# piezo-buffer-and-preamp-ritter_coppercla.net
KiCad netlist of a schematic drawn in EAGLE
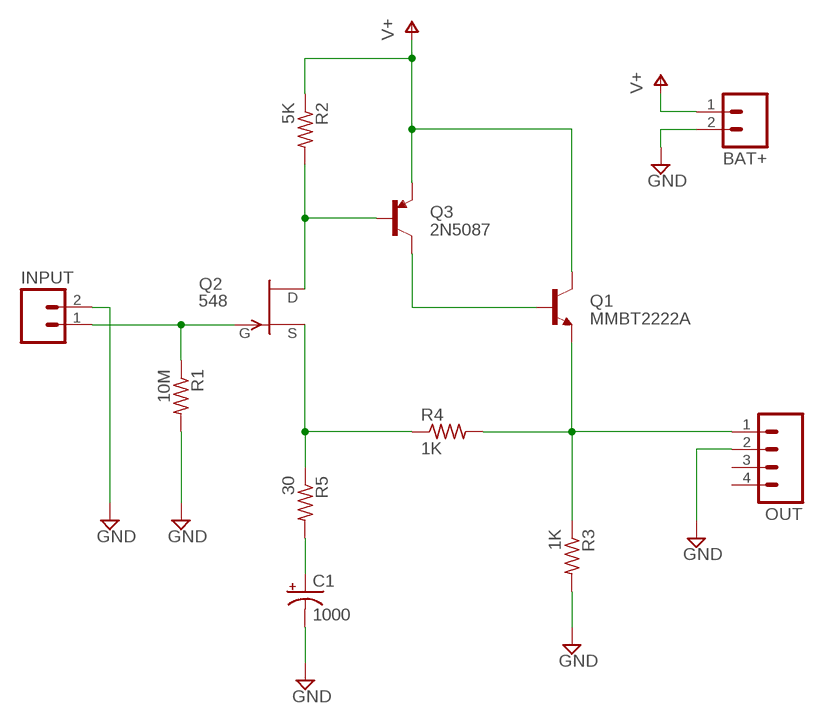
[diagram p0: schematic, sheet 1]

(export (version "E")
  (design (tool "Eeschema 10.0.6"))
  (components
    (comp (ref "BAT+")
      (value "M02LOCK")
      (footprint "eagle-import:1X02_LOCK")
      (libsource (lib "eagle-import") (part "M02LOCK"))
    )
    (comp (ref "C1")
      (value "1000")
      (footprint "eagle-import:CPOL-RADIAL-10UF-25V")
      (libsource (lib "eagle-import") (part "CAP_POLPTH2"))
    )
    (comp (ref "INPUT")
      (value "M02LOCK")
      (footprint "eagle-import:1X02_LOCK")
      (libsource (lib "eagle-import") (part "M02LOCK"))
    )
    (comp (ref "OUT")
      (value "M04PTH")
      (footprint "eagle-import:1X04")
      (libsource (lib "eagle-import") (part "M04PTH"))
    )
    (comp (ref "Q1")
      (value "MMBT2222A")
      (footprint "eagle-import:TO-92")
      (libsource (lib "eagle-import") (part "TRANSISTOR_NPNTO92"))
    )
    (comp (ref "Q2")
      (value "548")
      (footprint "eagle-import:TO-92")
      (libsource (lib "eagle-import") (part "?548"))
    )
    (comp (ref "Q3")
      (value "2N5087")
      (footprint "eagle-import:TO-92")
      (libsource (lib "eagle-import") (part "TRANSISTOR_PNPTO92"))
    )
    (comp (ref "R1")
      (value "10M")
      (footprint "eagle-import:VMTA55")
      (libsource (lib "eagle-import") (part "R-US_VMTA55"))
    )
    (comp (ref "R2")
      (value "5K")
      (footprint "eagle-import:VMTA55")
      (libsource (lib "eagle-import") (part "R-US_VMTA55"))
    )
    (comp (ref "R3")
      (value "1K")
      (footprint "eagle-import:VMTA55")
      (libsource (lib "eagle-import") (part "R-US_VMTA55"))
    )
    (comp (ref "R4")
      (value "1K")
      (footprint "eagle-import:VMTA55")
      (libsource (lib "eagle-import") (part "R-US_VMTA55"))
    )
    (comp (ref "R5")
      (value "30")
      (footprint "eagle-import:VMTA55")
      (libsource (lib "eagle-import") (part "R-US_VMTA55"))
    )
  )
  (nets
    (net (code "1") (name "GND") (class "Default")
      (node (ref "BAT+") (pin "2") (pinfunction "2_2") (pintype "passive"))
      (node (ref "C1") (pin "2") (pinfunction "-_2") (pintype "passive"))
      (node (ref "INPUT") (pin "2") (pinfunction "2_2") (pintype "passive"))
      (node (ref "OUT") (pin "2") (pinfunction "2_2") (pintype "passive"))
      (node (ref "R1") (pin "2") (pinfunction "2_2") (pintype "passive"))
      (node (ref "R3") (pin "2") (pinfunction "2_2") (pintype "passive"))
    )
    (net (code "2") (name "Net-(C1-+)") (class "Default")
      (node (ref "C1") (pin "1") (pinfunction "+_1") (pintype "passive"))
      (node (ref "R5") (pin "2") (pinfunction "2_2") (pintype "passive"))
    )
    (net (code "3") (name "Net-(Q1-B)") (class "Default")
      (node (ref "Q1") (pin "2") (pinfunction "B_2") (pintype "passive"))
      (node (ref "Q3") (pin "3") (pinfunction "C_3") (pintype "passive"))
    )
    (net (code "4") (name "Net-(Q1-E)") (class "Default")
      (node (ref "OUT") (pin "1") (pinfunction "1_1") (pintype "passive"))
      (node (ref "Q1") (pin "1") (pinfunction "E_1") (pintype "passive"))
      (node (ref "R3") (pin "1") (pinfunction "1_1") (pintype "passive"))
      (node (ref "R4") (pin "2") (pinfunction "2_2") (pintype "passive"))
    )
    (net (code "5") (name "Net-(Q2-D)") (class "Default")
      (node (ref "Q2") (pin "3") (pinfunction "D_3") (pintype "passive"))
      (node (ref "Q3") (pin "2") (pinfunction "B_2") (pintype "passive"))
      (node (ref "R2") (pin "2") (pinfunction "2_2") (pintype "passive"))
    )
    (net (code "6") (name "Net-(Q2-G)") (class "Default")
      (node (ref "INPUT") (pin "1") (pinfunction "1_1") (pintype "passive"))
      (node (ref "Q2") (pin "1") (pinfunction "G_1") (pintype "passive"))
      (node (ref "R1") (pin "1") (pinfunction "1_1") (pintype "passive"))
    )
    (net (code "7") (name "Net-(Q2-S)") (class "Default")
      (node (ref "Q2") (pin "2") (pinfunction "S_2") (pintype "passive"))
      (node (ref "R4") (pin "1") (pinfunction "1_1") (pintype "passive"))
      (node (ref "R5") (pin "1") (pinfunction "1_1") (pintype "passive"))
    )
    (net (code "8") (name "V+") (class "Default")
      (node (ref "BAT+") (pin "1") (pinfunction "1_1") (pintype "passive"))
      (node (ref "Q1") (pin "3") (pinfunction "C_3") (pintype "passive"))
      (node (ref "Q3") (pin "1") (pinfunction "E_1") (pintype "passive"))
      (node (ref "R2") (pin "1") (pinfunction "1_1") (pintype "passive"))
    )
    (net (code "9") (name "unconnected-(OUT-Pad3)") (class "Default")
      (node (ref "OUT") (pin "3") (pinfunction "3_3") (pintype "passive"))
    )
    (net (code "10") (name "unconnected-(OUT-Pad4)") (class "Default")
      (node (ref "OUT") (pin "4") (pinfunction "4_4") (pintype "passive"))
    )
  )
)
